# prototype2.net
KiCad netlist of a schematic drawn in EAGLE
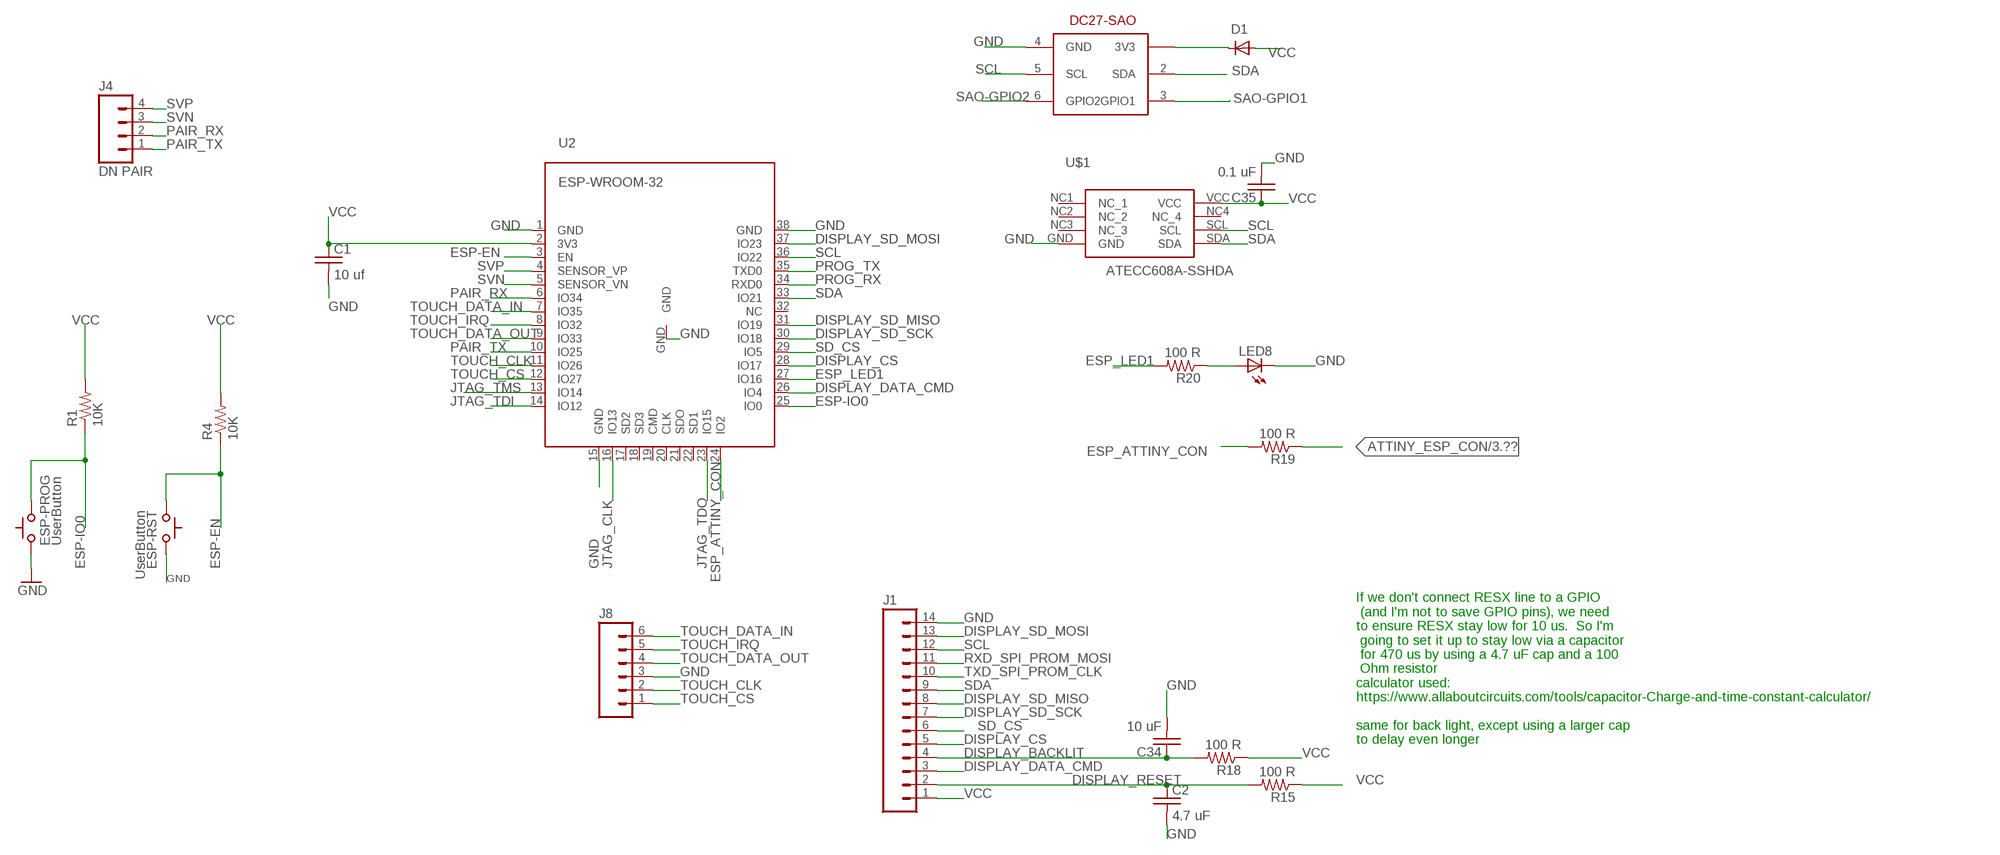
[diagram p0: schematic, sheet 1]
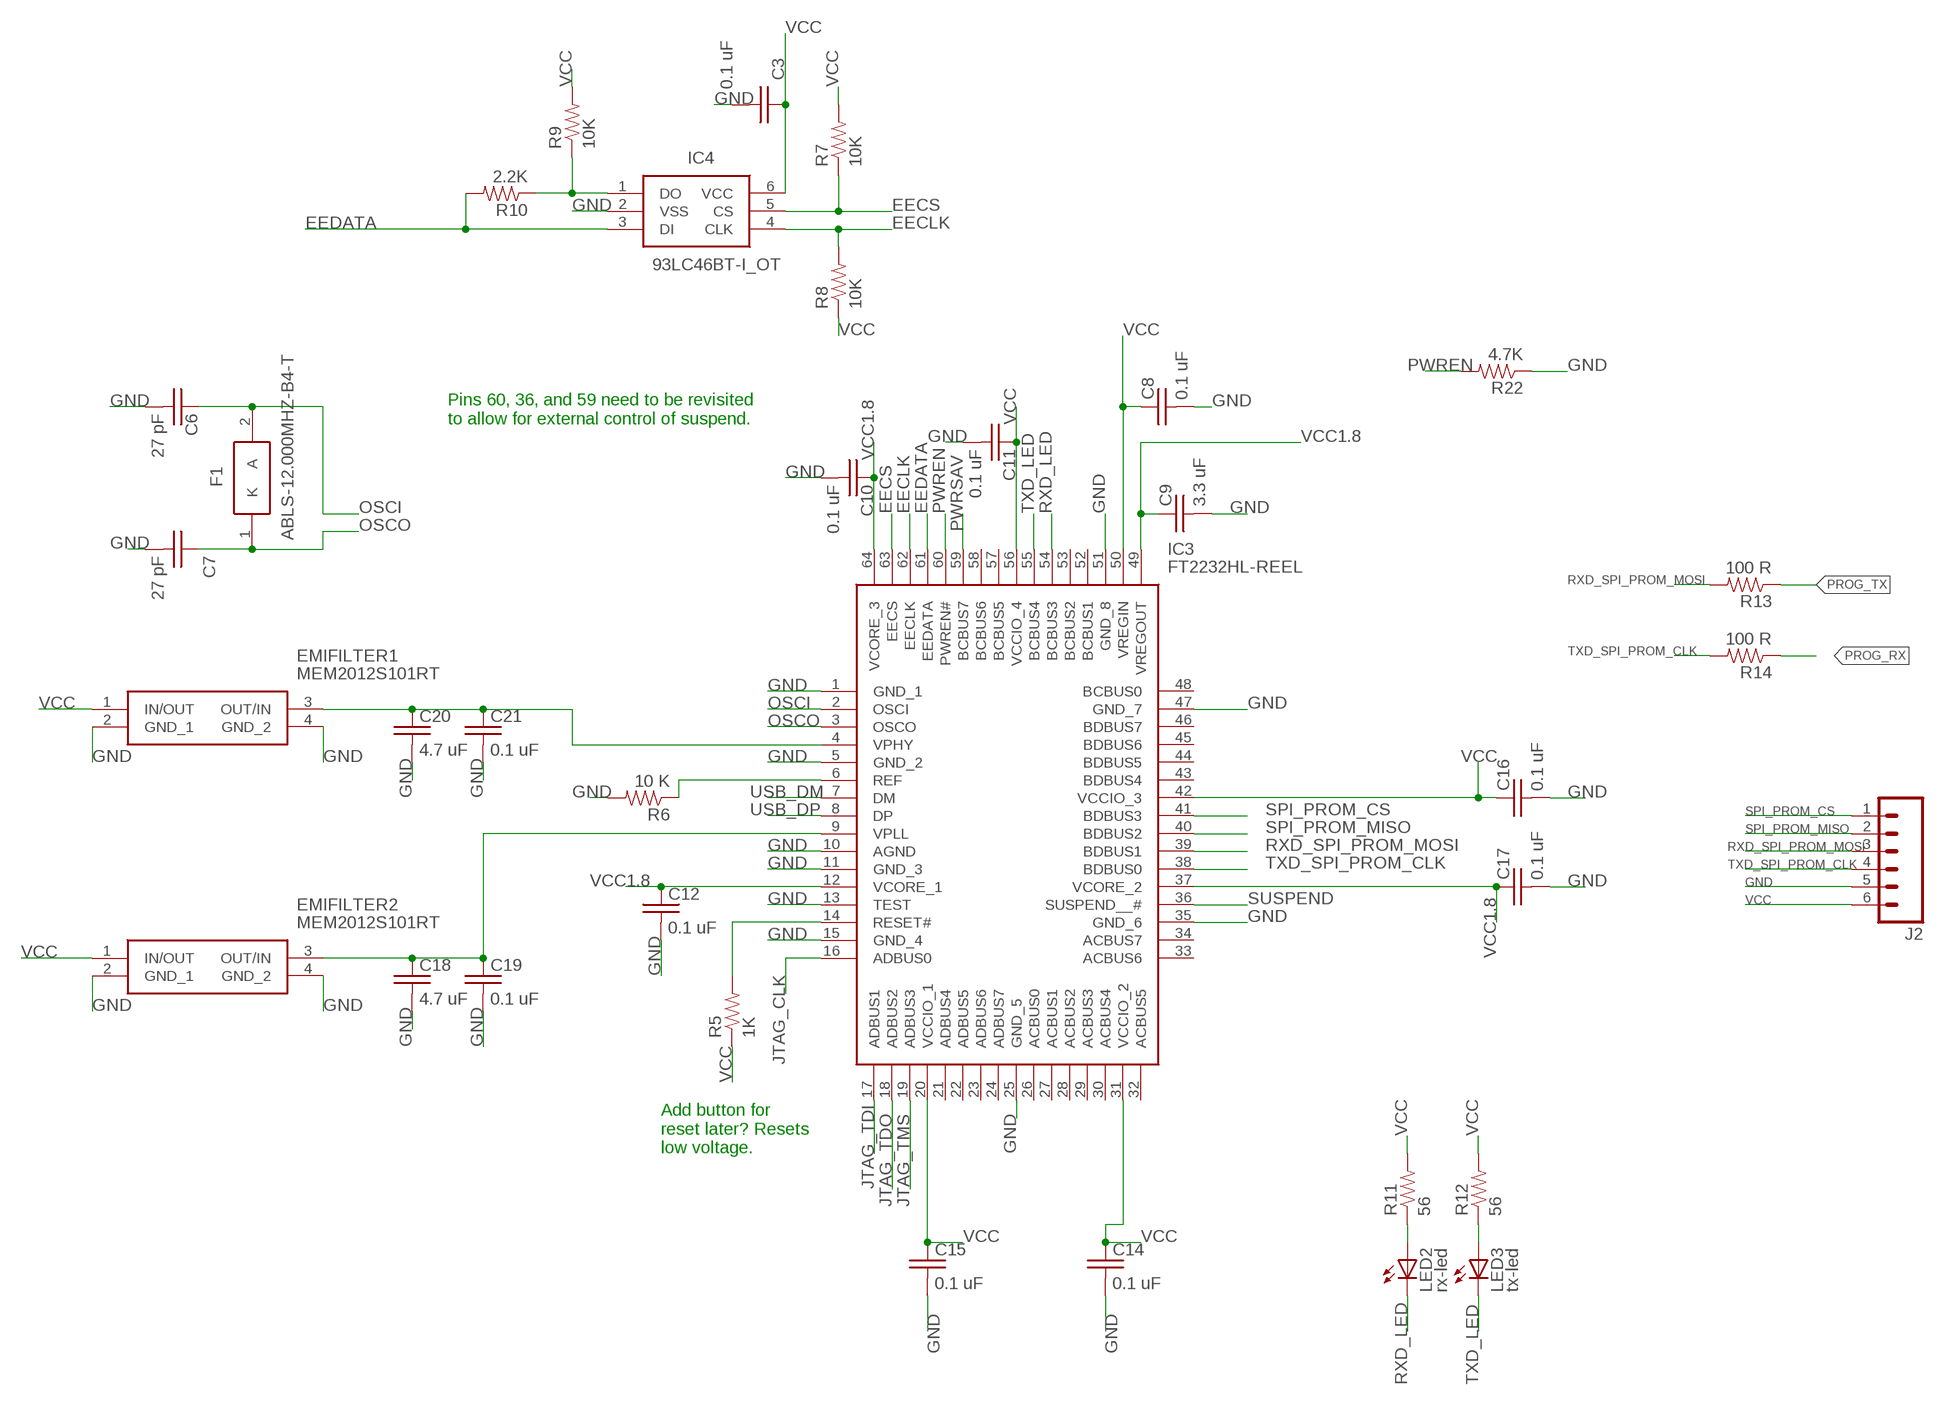
[diagram p1: schematic, sheet 2]
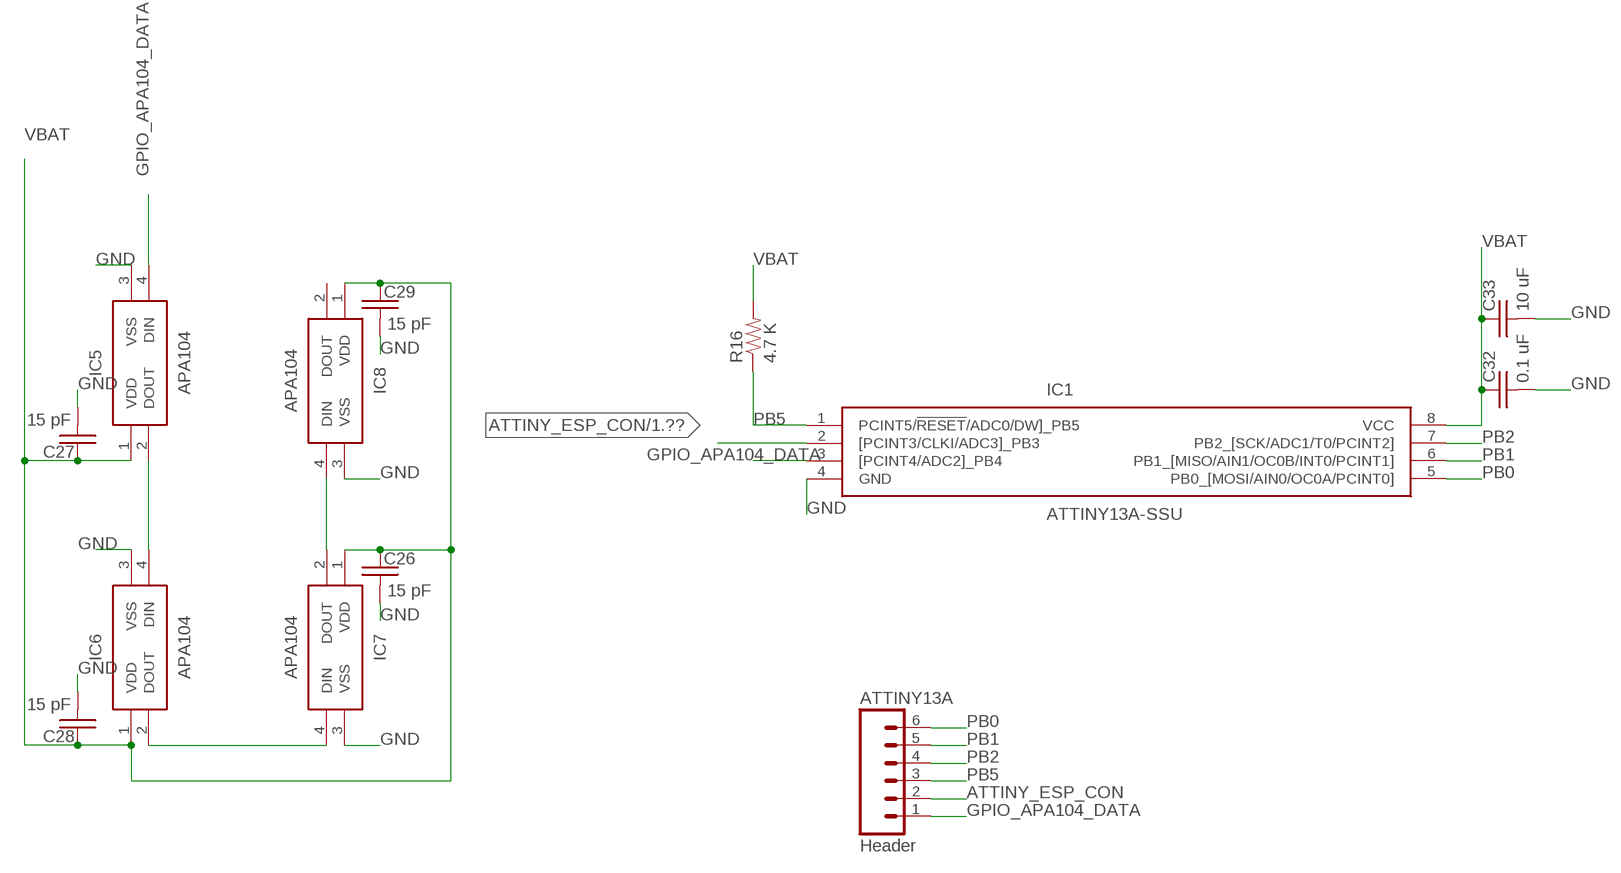
[diagram p2: schematic, sheet 3]
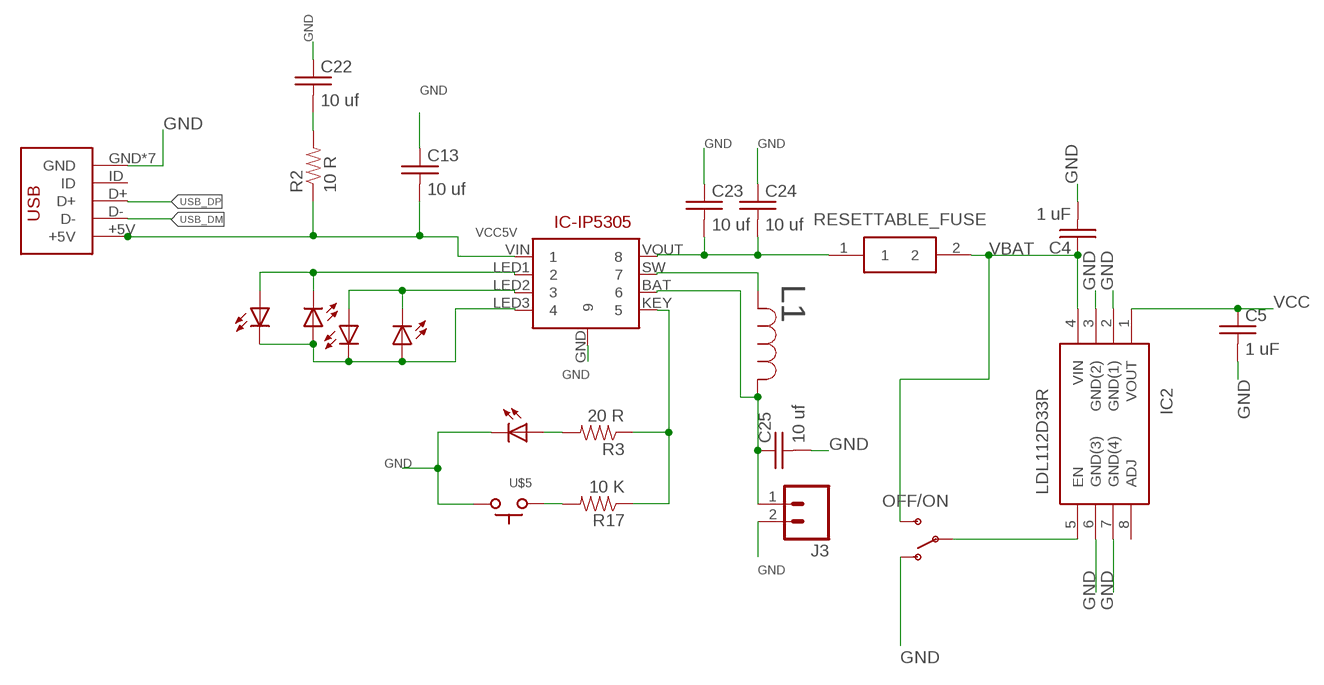
[diagram p3: schematic, sheet 4]
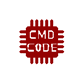
[diagram p4: schematic, sheet 5]

(export (version "E")
  (design (tool "Eeschema 10.0.6"))
  (components
    (comp (ref "ATTINY13A")
      (value "Header")
      (footprint "eagle-import:1X06")
      (libsource (lib "eagle-import") (part "M06SILK_FEMALE_PTH"))
    )
    (comp (ref "C26")
      (value "15 pF")
      (footprint "eagle-import:C0805")
      (libsource (lib "eagle-import") (part "C-USC0805"))
    )
    (comp (ref "C27")
      (value "15 pF")
      (footprint "eagle-import:C0805")
      (libsource (lib "eagle-import") (part "C-USC0805"))
    )
    (comp (ref "C28")
      (value "15 pF")
      (footprint "eagle-import:C0805")
      (libsource (lib "eagle-import") (part "C-USC0805"))
    )
    (comp (ref "C29")
      (value "15 pF")
      (footprint "eagle-import:C0805")
      (libsource (lib "eagle-import") (part "C-USC0805"))
    )
    (comp (ref "C32")
      (value "0.1 uF")
      (footprint "eagle-import:C0805")
      (libsource (lib "eagle-import") (part "C-USC0805"))
    )
    (comp (ref "C33")
      (value "10 uF")
      (footprint "eagle-import:C0805")
      (libsource (lib "eagle-import") (part "C-USC0805"))
    )
    (comp (ref "IC1")
      (value "ATTINY13A-SSU")
      (footprint "eagle-import:SOIC127P600X175-8N")
      (fields (field (name "MOUSER_PART_NUMBER") "556-ATTINY13A-SSU"))
      (libsource (lib "eagle-import") (part "ATTINY13A-SSU"))
    )
    (comp (ref "IC5")
      (value "APA104")
      (footprint "eagle-import:APA104")
      (libsource (lib "eagle-import") (part "APA104"))
    )
    (comp (ref "IC6")
      (value "APA104")
      (footprint "eagle-import:APA104")
      (libsource (lib "eagle-import") (part "APA104"))
    )
    (comp (ref "IC7")
      (value "APA104")
      (footprint "eagle-import:APA104")
      (libsource (lib "eagle-import") (part "APA104"))
    )
    (comp (ref "IC8")
      (value "APA104")
      (footprint "eagle-import:APA104")
      (libsource (lib "eagle-import") (part "APA104"))
    )
    (comp (ref "R16")
      (value "4.7 K")
      (footprint "eagle-import:0805")
      (libsource (lib "eagle-import") (part "passives_RESISTOR0805-RES"))
    )
    (comp (ref "U$3")
      (value "CMD_C0DE_LOGOCMD_CODE_LOGO_TOP_COPPER")
      (footprint "eagle-import:CMD_C0DE_LOGO_TOP_COPPER")
      (libsource (lib "eagle-import") (part "CMD_C0DE_LOGOCMD_CODE_LOGO_TOP_COPPER"))
    )
    (comp (ref "C1")
      (value "10 uf")
      (footprint "eagle-import:C0805")
      (libsource (lib "eagle-import") (part "C-USC0805"))
    )
    (comp (ref "C2")
      (value "4.7 uF")
      (footprint "eagle-import:C0805")
      (libsource (lib "eagle-import") (part "C-USC0805"))
    )
    (comp (ref "C34")
      (value "10 uF")
      (footprint "eagle-import:C0805")
      (libsource (lib "eagle-import") (part "C-USC0805"))
    )
    (comp (ref "C35")
      (value "0.1 uF")
      (footprint "eagle-import:C0805")
      (libsource (lib "eagle-import") (part "C-USC0805"))
    )
    (comp (ref "D1")
      (value "DIODESMA")
      (footprint "eagle-import:SMA-DIODE")
      (libsource (lib "eagle-import") (part "DIODESMA"))
    )
    (comp (ref "ESP-PROG")
      (value "UserButton")
      (footprint "eagle-import:TACTILE-2PIN-NARROW")
      (libsource (lib "eagle-import") (part "SWITCH_TACTILETACTILE-2PIN-NARROW"))
    )
    (comp (ref "ESP-RST")
      (value "UserButton")
      (footprint "eagle-import:TACTILE-2PIN-NARROW")
      (libsource (lib "eagle-import") (part "SWITCH_TACTILETACTILE-2PIN-NARROW"))
    )
    (comp (ref "J1")
      (value "M14")
      (footprint "eagle-import:1X14")
      (libsource (lib "eagle-import") (part "M14"))
    )
    (comp (ref "J4")
      (value "DN PAIR")
      (footprint "eagle-import:1X04")
      (libsource (lib "eagle-import") (part "M04PTH"))
    )
    (comp (ref "J8")
      (value "M06NO_SILK_YES_STOP")
      (footprint "eagle-import:1X06_NO_SILK_YES_STOP")
      (libsource (lib "eagle-import") (part "M06NO_SILK_YES_STOP"))
    )
    (comp (ref "LED8")
      (value "LED3MM")
      (footprint "eagle-import:LED3MM")
      (libsource (lib "eagle-import") (part "LED3MM"))
    )
    (comp (ref "R1")
      (value "10K")
      (footprint "eagle-import:0805")
      (libsource (lib "eagle-import") (part "RESISTOR0805-RES"))
    )
    (comp (ref "R4")
      (value "10K")
      (footprint "eagle-import:0805")
      (libsource (lib "eagle-import") (part "RESISTOR0805-RES"))
    )
    (comp (ref "R15")
      (value "100 R")
      (footprint "eagle-import:0805")
      (libsource (lib "eagle-import") (part "RESISTOR0805-RES"))
    )
    (comp (ref "R18")
      (value "100 R")
      (footprint "eagle-import:0805")
      (libsource (lib "eagle-import") (part "RESISTOR0805-RES"))
    )
    (comp (ref "R19")
      (value "100 R")
      (footprint "eagle-import:0805")
      (libsource (lib "eagle-import") (part "RESISTOR0805-RES"))
    )
    (comp (ref "R20")
      (value "100 R")
      (footprint "eagle-import:0805")
      (libsource (lib "eagle-import") (part "RESISTOR0805-RES"))
    )
    (comp (ref "U$1")
      (value "ATECC608A-SSHDA")
      (footprint "eagle-import:8-SOIC")
      (libsource (lib "eagle-import") (part "ATECC608A-SSHDA"))
    )
    (comp (ref "U$4")
      (value "DC-27-SAO")
      (footprint "eagle-import:3X2")
      (libsource (lib "eagle-import") (part "DC-27-SAO"))
    )
    (comp (ref "U2")
      (value "ESP-WROOM-32")
      (footprint "eagle-import:ESP-WROOM-32")
      (libsource (lib "eagle-import") (part "ESP-WROOM-32"))
    )
    (comp (ref "C3")
      (value "0.1 uF")
      (footprint "eagle-import:C0805")
      (libsource (lib "eagle-import") (part "C-USC0805"))
    )
    (comp (ref "C6")
      (value "27 pF")
      (footprint "eagle-import:C0805")
      (libsource (lib "eagle-import") (part "C-USC0805"))
    )
    (comp (ref "C7")
      (value "27 pF")
      (footprint "eagle-import:C0805")
      (libsource (lib "eagle-import") (part "C-USC0805"))
    )
    (comp (ref "C8")
      (value "0.1 uF")
      (footprint "eagle-import:C0805")
      (libsource (lib "eagle-import") (part "C-USC0805"))
    )
    (comp (ref "C9")
      (value "3.3 uF")
      (footprint "eagle-import:C0805")
      (libsource (lib "eagle-import") (part "C-USC0805"))
    )
    (comp (ref "C10")
      (value "0.1 uF")
      (footprint "eagle-import:C0805")
      (libsource (lib "eagle-import") (part "C-USC0805"))
    )
    (comp (ref "C11")
      (value "0.1 uF")
      (footprint "eagle-import:C0805")
      (libsource (lib "eagle-import") (part "C-USC0805"))
    )
    (comp (ref "C12")
      (value "0.1 uF")
      (footprint "eagle-import:C0805")
      (libsource (lib "eagle-import") (part "C-USC0805"))
    )
    (comp (ref "C14")
      (value "0.1 uF")
      (footprint "eagle-import:C0805")
      (libsource (lib "eagle-import") (part "C-USC0805"))
    )
    (comp (ref "C15")
      (value "0.1 uF")
      (footprint "eagle-import:C0805")
      (libsource (lib "eagle-import") (part "C-USC0805"))
    )
    (comp (ref "C16")
      (value "0.1 uF")
      (footprint "eagle-import:C0805")
      (libsource (lib "eagle-import") (part "C-USC0805"))
    )
    (comp (ref "C17")
      (value "0.1 uF")
      (footprint "eagle-import:C0805")
      (libsource (lib "eagle-import") (part "C-USC0805"))
    )
    (comp (ref "C18")
      (value "4.7 uF")
      (footprint "eagle-import:C0805")
      (libsource (lib "eagle-import") (part "C-USC0805"))
    )
    (comp (ref "C19")
      (value "0.1 uF")
      (footprint "eagle-import:C0805")
      (libsource (lib "eagle-import") (part "C-USC0805"))
    )
    (comp (ref "C20")
      (value "4.7 uF")
      (footprint "eagle-import:C0805")
      (libsource (lib "eagle-import") (part "C-USC0805"))
    )
    (comp (ref "C21")
      (value "0.1 uF")
      (footprint "eagle-import:C0805")
      (libsource (lib "eagle-import") (part "C-USC0805"))
    )
    (comp (ref "EMIFILTER1")
      (value "MEM2012S101RT")
      (footprint "eagle-import:MEM2012S101RT")
      (libsource (lib "eagle-import") (part "MEM2012S101RT"))
    )
    (comp (ref "EMIFILTER2")
      (value "MEM2012S101RT")
      (footprint "eagle-import:MEM2012S101RT")
      (libsource (lib "eagle-import") (part "MEM2012S101RT"))
    )
    (comp (ref "F1")
      (value "ABLS-12.000MHZ-B4-T")
      (footprint "eagle-import:HC_49US-(AT49)_1")
      (fields
        (field (name "MOUSER_PART_NUMBER") "815-ABLS-12.0M-T")
        (field (name "RS_PART_NUMBER") "1710207")
      )
      (libsource (lib "eagle-import") (part "ABLS-12.000MHZ-B4-T"))
    )
    (comp (ref "IC3")
      (value "FT2232HL-REEL")
      (footprint "eagle-import:QFP50P1200X1200X160-64N")
      (fields (field (name "MOUSER_PART_NUMBER") "895-FT2232HL"))
      (libsource (lib "eagle-import") (part "FT2232HL-REEL"))
    )
    (comp (ref "IC4")
      (value "93LC46BT-I_OT")
      (footprint "eagle-import:SOT95P270X145-6N")
      (fields
        (field (name "MANUFACTURER_PART_NUMBER") "93LC46BT-I/OT")
        (field (name "MOUSER_PART_NUMBER") "579-93LC46BT-I/OT")
      )
      (libsource (lib "eagle-import") (part "93LC46BT-I_OT"))
    )
    (comp (ref "J2")
      (value "M06SILK_FEMALE_PTH")
      (footprint "eagle-import:1X06")
      (libsource (lib "eagle-import") (part "M06SILK_FEMALE_PTH"))
    )
    (comp (ref "LED2")
      (value "rx-led")
      (footprint "eagle-import:LED3MM")
      (libsource (lib "eagle-import") (part "LED3MM"))
    )
    (comp (ref "LED3")
      (value "tx-led")
      (footprint "eagle-import:LED3MM")
      (libsource (lib "eagle-import") (part "LED3MM"))
    )
    (comp (ref "R5")
      (value "1K")
      (footprint "eagle-import:0805")
      (libsource (lib "eagle-import") (part "passives_RESISTOR0805-RES"))
    )
    (comp (ref "R6")
      (value "10 K")
      (footprint "eagle-import:0805")
      (libsource (lib "eagle-import") (part "passives_RESISTOR0805-RES"))
    )
    (comp (ref "R7")
      (value "10K")
      (footprint "eagle-import:0805")
      (libsource (lib "eagle-import") (part "passives_RESISTOR0805-RES"))
    )
    (comp (ref "R8")
      (value "10K")
      (footprint "eagle-import:0805")
      (libsource (lib "eagle-import") (part "passives_RESISTOR0805-RES"))
    )
    (comp (ref "R9")
      (value "10K")
      (footprint "eagle-import:0805")
      (libsource (lib "eagle-import") (part "passives_RESISTOR0805-RES"))
    )
    (comp (ref "R10")
      (value "2.2K")
      (footprint "eagle-import:0805")
      (libsource (lib "eagle-import") (part "passives_RESISTOR0805-RES"))
    )
    (comp (ref "R11")
      (value "56")
      (footprint "eagle-import:0805")
      (libsource (lib "eagle-import") (part "passives_RESISTOR0805-RES"))
    )
    (comp (ref "R12")
      (value "56")
      (footprint "eagle-import:0805")
      (libsource (lib "eagle-import") (part "passives_RESISTOR0805-RES"))
    )
    (comp (ref "R13")
      (value "100 R")
      (footprint "eagle-import:0805")
      (libsource (lib "eagle-import") (part "passives_RESISTOR0805-RES"))
    )
    (comp (ref "R14")
      (value "100 R")
      (footprint "eagle-import:0805")
      (libsource (lib "eagle-import") (part "passives_RESISTOR0805-RES"))
    )
    (comp (ref "R22")
      (value "4.7K")
      (footprint "eagle-import:0805")
      (libsource (lib "eagle-import") (part "passives_RESISTOR0805-RES"))
    )
    (comp (ref "C4")
      (value "1 uF")
      (footprint "eagle-import:C0805")
      (libsource (lib "eagle-import") (part "C-USC0805"))
    )
    (comp (ref "C5")
      (value "1 uF")
      (footprint "eagle-import:C0805")
      (libsource (lib "eagle-import") (part "C-USC0805"))
    )
    (comp (ref "C13")
      (value "10 uf")
      (footprint "eagle-import:C0805")
      (libsource (lib "eagle-import") (part "C-USC0805"))
    )
    (comp (ref "C22")
      (value "10 uf")
      (footprint "eagle-import:C0805")
      (libsource (lib "eagle-import") (part "C-USC0805"))
    )
    (comp (ref "C23")
      (value "10 uf")
      (footprint "eagle-import:C0805")
      (libsource (lib "eagle-import") (part "C-USC0805"))
    )
    (comp (ref "C24")
      (value "10 uf")
      (footprint "eagle-import:C0805")
      (libsource (lib "eagle-import") (part "C-USC0805"))
    )
    (comp (ref "C25")
      (value "10 uf")
      (footprint "eagle-import:C0805")
      (libsource (lib "eagle-import") (part "C-USC0805"))
    )
    (comp (ref "IC-IP5305")
      (value "IP5305ESOP8")
      (footprint "eagle-import:SOIC127P600X165-8")
      (libsource (lib "eagle-import") (part "IP5305ESOP8"))
    )
    (comp (ref "IC2")
      (value "LDL112D33R")
      (footprint "eagle-import:SOIC127P600X175-8N")
      (libsource (lib "eagle-import") (part "LDL112D33R"))
    )
    (comp (ref "J3")
      (value "M02PTH")
      (footprint "eagle-import:1X02")
      (libsource (lib "eagle-import") (part "M02PTH"))
    )
    (comp (ref "L1")
      (value "NRS4018T2R2MDGJ")
      (footprint "eagle-import:IND_TAIYO_NRS4018")
      (libsource (lib "eagle-import") (part "NRS4018T2R2MDGJ"))
    )
    (comp (ref "LED1")
      (value "LED3MM")
      (footprint "eagle-import:LED3MM")
      (libsource (lib "eagle-import") (part "LED3MM"))
    )
    (comp (ref "LED4")
      (value "LED3MM")
      (footprint "eagle-import:LED3MM")
      (libsource (lib "eagle-import") (part "LED3MM"))
    )
    (comp (ref "LED5")
      (value "LED3MM")
      (footprint "eagle-import:LED3MM")
      (libsource (lib "eagle-import") (part "LED3MM"))
    )
    (comp (ref "LED6")
      (value "LED3MM")
      (footprint "eagle-import:LED3MM")
      (libsource (lib "eagle-import") (part "LED3MM"))
    )
    (comp (ref "LED7")
      (value "LED3MM")
      (footprint "eagle-import:LED3MM")
      (libsource (lib "eagle-import") (part "LED3MM"))
    )
    (comp (ref "OFF/ON")
      (value "SWITCH-SPSTPTH")
      (footprint "eagle-import:SWITCH-SPDT")
      (libsource (lib "eagle-import") (part "SWITCH-SPSTPTH"))
    )
    (comp (ref "R2")
      (value "10 R")
      (footprint "eagle-import:0805")
      (libsource (lib "eagle-import") (part "passives_RESISTOR0805-RES"))
    )
    (comp (ref "R3")
      (value "20 R")
      (footprint "eagle-import:0805")
      (libsource (lib "eagle-import") (part "passives_RESISTOR0805-RES"))
    )
    (comp (ref "R17")
      (value "10 K")
      (footprint "eagle-import:0805")
      (libsource (lib "eagle-import") (part "passives_RESISTOR0805-RES"))
    )
    (comp (ref "RESETTABLE_FUSE")
      (value "0ZCJ0050FF2G")
      (footprint "eagle-import:FUSC3216X55N")
      (libsource (lib "eagle-import") (part "0ZCJ0050FF2G"))
    )
    (comp (ref "U$2")
      (value "DX4R005JJ2DX4R005JJ2")
      (footprint "eagle-import:DX4R005JJ2")
      (libsource (lib "eagle-import") (part "DX4R005JJ2DX4R005JJ2"))
    )
    (comp (ref "U$5")
      (value "SWITCH_TACTILETACTILE-2PIN-NARROW")
      (footprint "eagle-import:TACTILE-2PIN-NARROW")
      (libsource (lib "eagle-import") (part "switches_SWITCH_TACTILETACTILE-2PIN-NARROW"))
    )
  )
  (nets
    (net (code "1") (name "ATTINY_ESP_CON") (class "Default")
      (node (ref "ATTINY13A") (pin "2") (pinfunction "2_2") (pintype "passive"))
      (node (ref "IC1") (pin "2") (pinfunction "[PCINT3/CLKI/ADC3]_PB3_2") (pintype "input"))
      (node (ref "R19") (pin "1") (pinfunction "1_1") (pintype "passive"))
    )
    (net (code "2") (name "DISPLAY_BACKLIT") (class "Default")
      (node (ref "C34") (pin "1") (pinfunction "1_1") (pintype "passive"))
      (node (ref "J1") (pin "4") (pinfunction "4_4") (pintype "passive"))
      (node (ref "R18") (pin "2") (pinfunction "2_2") (pintype "passive"))
    )
    (net (code "3") (name "DISPLAY_CS") (class "Default")
      (node (ref "J1") (pin "5") (pinfunction "5_5") (pintype "passive"))
      (node (ref "U2") (pin "28") (pinfunction "IO17_28") (pintype "bidirectional"))
    )
    (net (code "4") (name "DISPLAY_DATA_CMD") (class "Default")
      (node (ref "J1") (pin "3") (pinfunction "3_3") (pintype "passive"))
      (node (ref "U2") (pin "26") (pinfunction "IO4_26") (pintype "bidirectional"))
    )
    (net (code "5") (name "DISPLAY_RESET") (class "Default")
      (node (ref "C2") (pin "1") (pinfunction "1_1") (pintype "passive"))
      (node (ref "J1") (pin "2") (pinfunction "2_2") (pintype "passive"))
      (node (ref "R15") (pin "2") (pinfunction "2_2") (pintype "passive"))
    )
    (net (code "6") (name "DISPLAY_SD_MISO") (class "Default")
      (node (ref "J1") (pin "8") (pinfunction "8_8") (pintype "passive"))
      (node (ref "U2") (pin "31") (pinfunction "IO19_31") (pintype "bidirectional"))
    )
    (net (code "7") (name "DISPLAY_SD_MOSI") (class "Default")
      (node (ref "J1") (pin "13") (pinfunction "13_13") (pintype "passive"))
      (node (ref "U2") (pin "37") (pinfunction "IO23_37") (pintype "bidirectional"))
    )
    (net (code "8") (name "DISPLAY_SD_SCK") (class "Default")
      (node (ref "J1") (pin "7") (pinfunction "7_7") (pintype "passive"))
      (node (ref "U2") (pin "30") (pinfunction "IO18_30") (pintype "bidirectional"))
    )
    (net (code "9") (name "EECLK") (class "Default")
      (node (ref "IC3") (pin "62") (pinfunction "EECLK_62") (pintype "bidirectional"))
      (node (ref "IC4") (pin "4") (pinfunction "CLK_4") (pintype "input"))
      (node (ref "R8") (pin "2") (pinfunction "2_2") (pintype "passive"))
    )
    (net (code "10") (name "EECS") (class "Default")
      (node (ref "IC3") (pin "63") (pinfunction "EECS_63") (pintype "bidirectional"))
      (node (ref "IC4") (pin "5") (pinfunction "CS_5") (pintype "input"))
      (node (ref "R7") (pin "1") (pinfunction "1_1") (pintype "passive"))
    )
    (net (code "11") (name "EEDATA") (class "Default")
      (node (ref "IC3") (pin "61") (pinfunction "EEDATA_61") (pintype "bidirectional"))
      (node (ref "IC4") (pin "3") (pinfunction "DI_3") (pintype "bidirectional"))
      (node (ref "R10") (pin "2") (pinfunction "2_2") (pintype "passive"))
    )
    (net (code "12") (name "ESP-EN") (class "Default")
      (node (ref "ESP-RST") (pin "P$2") (pinfunction "C_P$2") (pintype "passive"))
      (node (ref "R4") (pin "1") (pinfunction "1_1") (pintype "passive"))
      (node (ref "U2") (pin "3") (pinfunction "EN_3") (pintype "bidirectional"))
    )
    (net (code "13") (name "ESP-IO0") (class "Default")
      (node (ref "ESP-PROG") (pin "P$1") (pinfunction "A_P$1") (pintype "passive"))
      (node (ref "R1") (pin "1") (pinfunction "1_1") (pintype "passive"))
      (node (ref "U2") (pin "25") (pinfunction "IO0_25") (pintype "bidirectional"))
    )
    (net (code "14") (name "ESP_ATTINY_CON") (class "Default")
      (node (ref "R19") (pin "2") (pinfunction "2_2") (pintype "passive"))
      (node (ref "U2") (pin "24") (pinfunction "IO2_24") (pintype "bidirectional"))
    )
    (net (code "15") (name "ESP_LED1") (class "Default")
      (node (ref "R20") (pin "2") (pinfunction "2_2") (pintype "passive"))
      (node (ref "U2") (pin "27") (pinfunction "IO16_27") (pintype "bidirectional"))
    )
    (net (code "16") (name "GND") (class "Default")
      (node (ref "C1") (pin "2") (pinfunction "2_2") (pintype "passive"))
      (node (ref "C10") (pin "2") (pinfunction "2_2") (pintype "passive"))
      (node (ref "C11") (pin "2") (pinfunction "2_2") (pintype "passive"))
      (node (ref "C12") (pin "2") (pinfunction "2_2") (pintype "passive"))
      (node (ref "C13") (pin "1") (pinfunction "1_1") (pintype "passive"))
      (node (ref "C14") (pin "2") (pinfunction "2_2") (pintype "passive"))
      (node (ref "C15") (pin "2") (pinfunction "2_2") (pintype "passive"))
      (node (ref "C16") (pin "2") (pinfunction "2_2") (pintype "passive"))
      (node (ref "C17") (pin "2") (pinfunction "2_2") (pintype "passive"))
      (node (ref "C18") (pin "2") (pinfunction "2_2") (pintype "passive"))
      (node (ref "C19") (pin "2") (pinfunction "2_2") (pintype "passive"))
      (node (ref "C2") (pin "2") (pinfunction "2_2") (pintype "passive"))
      (node (ref "C20") (pin "2") (pinfunction "2_2") (pintype "passive"))
      (node (ref "C21") (pin "2") (pinfunction "2_2") (pintype "passive"))
      (node (ref "C22") (pin "1") (pinfunction "1_1") (pintype "passive"))
      (node (ref "C23") (pin "1") (pinfunction "1_1") (pintype "passive"))
      (node (ref "C24") (pin "1") (pinfunction "1_1") (pintype "passive"))
      (node (ref "C25") (pin "2") (pinfunction "2_2") (pintype "passive"))
      (node (ref "C26") (pin "2") (pinfunction "2_2") (pintype "passive"))
      (node (ref "C27") (pin "2") (pinfunction "2_2") (pintype "passive"))
      (node (ref "C28") (pin "2") (pinfunction "2_2") (pintype "passive"))
      (node (ref "C29") (pin "2") (pinfunction "2_2") (pintype "passive"))
      (node (ref "C3") (pin "2") (pinfunction "2_2") (pintype "passive"))
      (node (ref "C32") (pin "2") (pinfunction "2_2") (pintype "passive"))
      (node (ref "C33") (pin "2") (pinfunction "2_2") (pintype "passive"))
      (node (ref "C34") (pin "2") (pinfunction "2_2") (pintype "passive"))
      (node (ref "C35") (pin "2") (pinfunction "2_2") (pintype "passive"))
      (node (ref "C4") (pin "2") (pinfunction "2_2") (pintype "passive"))
      (node (ref "C5") (pin "2") (pinfunction "2_2") (pintype "passive"))
      (node (ref "C6") (pin "2") (pinfunction "2_2") (pintype "passive"))
      (node (ref "C7") (pin "2") (pinfunction "2_2") (pintype "passive"))
      (node (ref "C8") (pin "2") (pinfunction "2_2") (pintype "passive"))
      (node (ref "C9") (pin "2") (pinfunction "2_2") (pintype "passive"))
      (node (ref "EMIFILTER1") (pin "2") (pinfunction "GND_1_2") (pintype "bidirectional"))
      (node (ref "EMIFILTER1") (pin "4") (pinfunction "GND_2_4") (pintype "bidirectional"))
      (node (ref "EMIFILTER2") (pin "2") (pinfunction "GND_1_2") (pintype "bidirectional"))
      (node (ref "EMIFILTER2") (pin "4") (pinfunction "GND_2_4") (pintype "bidirectional"))
      (node (ref "ESP-PROG") (pin "P$2") (pinfunction "C_P$2") (pintype "passive"))
      (node (ref "ESP-RST") (pin "P$1") (pinfunction "A_P$1") (pintype "passive"))
      (node (ref "IC-IP5305") (pin "GND") (pinfunction "9_GND") (pintype "power_in"))
      (node (ref "IC1") (pin "4") (pinfunction "GND_4") (pintype "power_in"))
      (node (ref "IC2") (pin "2") (pinfunction "GND(1)_2") (pintype "bidirectional"))
      (node (ref "IC2") (pin "3") (pinfunction "GND(2)_3") (pintype "bidirectional"))
      (node (ref "IC2") (pin "6") (pinfunction "GND(3)_6") (pintype "bidirectional"))
      (node (ref "IC2") (pin "7") (pinfunction "GND(4)_7") (pintype "bidirectional"))
      (node (ref "IC3") (pin "1") (pinfunction "GND_1_1") (pintype "bidirectional"))
      (node (ref "IC3") (pin "10") (pinfunction "AGND_10") (pintype "bidirectional"))
      (node (ref "IC3") (pin "11") (pinfunction "GND_3_11") (pintype "bidirectional"))
      (node (ref "IC3") (pin "13") (pinfunction "TEST_13") (pintype "bidirectional"))
      (node (ref "IC3") (pin "15") (pinfunction "GND_4_15") (pintype "bidirectional"))
      (node (ref "IC3") (pin "25") (pinfunction "GND_5_25") (pintype "bidirectional"))
      (node (ref "IC3") (pin "35") (pinfunction "GND_6_35") (pintype "bidirectional"))
      (node (ref "IC3") (pin "47") (pinfunction "GND_7_47") (pintype "bidirectional"))
      (node (ref "IC3") (pin "5") (pinfunction "GND_2_5") (pintype "bidirectional"))
      (node (ref "IC3") (pin "51") (pinfunction "GND_8_51") (pintype "bidirectional"))
      (node (ref "IC4") (pin "2") (pinfunction "VSS_2") (pintype "power_in"))
      (node (ref "IC5") (pin "3") (pinfunction "VSS_3") (pintype "power_in"))
      (node (ref "IC6") (pin "3") (pinfunction "VSS_3") (pintype "power_in"))
      (node (ref "IC7") (pin "3") (pinfunction "VSS_3") (pintype "power_in"))
      (node (ref "IC8") (pin "3") (pinfunction "VSS_3") (pintype "power_in"))
      (node (ref "J1") (pin "14") (pinfunction "14_14") (pintype "passive"))
      (node (ref "J2") (pin "5") (pinfunction "5_5") (pintype "passive"))
      (node (ref "J3") (pin "2") (pinfunction "2_2") (pintype "passive"))
      (node (ref "J8") (pin "3") (pinfunction "3_3") (pintype "passive"))
      (node (ref "LED7") (pin "K") (pinfunction "C_K") (pintype "output"))
      (node (ref "LED8") (pin "K") (pinfunction "C_K") (pintype "output"))
      (node (ref "OFF/ON") (pin "1") (pinfunction "O_1") (pintype "passive"))
      (node (ref "R22") (pin "1") (pinfunction "1_1") (pintype "passive"))
      (node (ref "R6") (pin "2") (pinfunction "2_2") (pintype "passive"))
      (node (ref "U$1") (pin "GND") (pinfunction "GND_GND") (pintype "power_in"))
      (node (ref "U$2") (pin "GND") (pinfunction "GND_GND") (pintype "bidirectional"))
      (node (ref "U$2") (pin "P$10") (pinfunction "GND_P$10") (pintype "bidirectional"))
      (node (ref "U$2") (pin "P$11") (pinfunction "GND_P$11") (pintype "bidirectional"))
      (node (ref "U$2") (pin "P$6") (pinfunction "GND_P$6") (pintype "bidirectional"))
      (node (ref "U$2") (pin "P$7") (pinfunction "GND_P$7") (pintype "bidirectional"))
      (node (ref "U$2") (pin "P$8") (pinfunction "GND_P$8") (pintype "bidirectional"))
      (node (ref "U$2") (pin "P$9") (pinfunction "GND_P$9") (pintype "bidirectional"))
      (node (ref "U$4") (pin "4") (pinfunction "GND_4") (pintype "power_in"))
      (node (ref "U$5") (pin "P$1") (pinfunction "A_P$1") (pintype "passive"))
      (node (ref "U2") (pin "1") (pinfunction "GND_1") (pintype "bidirectional"))
      (node (ref "U2") (pin "15") (pinfunction "GND_15") (pintype "bidirectional"))
      (node (ref "U2") (pin "38") (pinfunction "GND_38") (pintype "bidirectional"))
      (node (ref "U2") (pin "GND") (pinfunction "GND_GND") (pintype "bidirectional"))
    )
    (net (code "17") (name "GPIO_APA104_DATA") (class "Default")
      (node (ref "ATTINY13A") (pin "1") (pinfunction "1_1") (pintype "passive"))
      (node (ref "IC1") (pin "3") (pinfunction "[PCINT4/ADC2]_PB4_3") (pintype "input"))
      (node (ref "IC5") (pin "4") (pinfunction "DIN_4") (pintype "input"))
    )
    (net (code "18") (name "JTAG_CLK") (class "Default")
      (node (ref "IC3") (pin "16") (pinfunction "ADBUS0_16") (pintype "bidirectional"))
      (node (ref "U2") (pin "16") (pinfunction "IO13_16") (pintype "bidirectional"))
    )
    (net (code "19") (name "JTAG_TDI") (class "Default")
      (node (ref "IC3") (pin "17") (pinfunction "ADBUS1_17") (pintype "bidirectional"))
      (node (ref "U2") (pin "14") (pinfunction "IO12_14") (pintype "bidirectional"))
    )
    (net (code "20") (name "JTAG_TDO") (class "Default")
      (node (ref "IC3") (pin "18") (pinfunction "ADBUS2_18") (pintype "bidirectional"))
      (node (ref "U2") (pin "23") (pinfunction "IO15_23") (pintype "bidirectional"))
    )
    (net (code "21") (name "JTAG_TMS") (class "Default")
      (node (ref "IC3") (pin "19") (pinfunction "ADBUS3_19") (pintype "bidirectional"))
      (node (ref "U2") (pin "13") (pinfunction "IO14_13") (pintype "bidirectional"))
    )
    (net (code "22") (name "Net-(C22-Pad2)") (class "Default")
      (node (ref "C22") (pin "2") (pinfunction "2_2") (pintype "passive"))
      (node (ref "R2") (pin "2") (pinfunction "2_2") (pintype "passive"))
    )
    (net (code "23") (name "Net-(EMIFILTER1-OUT{slash}IN)") (class "Default")
      (node (ref "C20") (pin "1") (pinfunction "1_1") (pintype "passive"))
      (node (ref "C21") (pin "1") (pinfunction "1_1") (pintype "passive"))
      (node (ref "EMIFILTER1") (pin "3") (pinfunction "OUT/IN_3") (pintype "bidirectional"))
      (node (ref "IC3") (pin "4") (pinfunction "VPHY_4") (pintype "bidirectional"))
    )
    (net (code "24") (name "Net-(EMIFILTER2-OUT{slash}IN)") (class "Default")
      (node (ref "C18") (pin "1") (pinfunction "1_1") (pintype "passive"))
      (node (ref "C19") (pin "1") (pinfunction "1_1") (pintype "passive"))
      (node (ref "EMIFILTER2") (pin "3") (pinfunction "OUT/IN_3") (pintype "bidirectional"))
      (node (ref "IC3") (pin "9") (pinfunction "VPLL_9") (pintype "bidirectional"))
    )
    (net (code "25") (name "Net-(IC-IP5305-2)") (class "Default")
      (node (ref "IC-IP5305") (pin "LED1") (pinfunction "2_LED1") (pintype "output"))
      (node (ref "LED1") (pin "A") (pinfunction "A_A") (pintype "input"))
      (node (ref "LED4") (pin "K") (pinfunction "C_K") (pintype "output"))
    )
    (net (code "26") (name "Net-(IC-IP5305-3)") (class "Default")
      (node (ref "IC-IP5305") (pin "LED2") (pinfunction "3_LED2") (pintype "output"))
      (node (ref "LED5") (pin "A") (pinfunction "A_A") (pintype "input"))
      (node (ref "LED6") (pin "K") (pinfunction "C_K") (pintype "output"))
    )
    (net (code "27") (name "Net-(IC-IP5305-4)") (class "Default")
      (node (ref "IC-IP5305") (pin "LED3") (pinfunction "4_LED3") (pintype "output"))
      (node (ref "LED1") (pin "K") (pinfunction "C_K") (pintype "output"))
      (node (ref "LED4") (pin "A") (pinfunction "A_A") (pintype "input"))
      (node (ref "LED5") (pin "K") (pinfunction "C_K") (pintype "output"))
      (node (ref "LED6") (pin "A") (pinfunction "A_A") (pintype "input"))
    )
    (net (code "28") (name "Net-(IC-IP5305-5)") (class "Default")
      (node (ref "IC-IP5305") (pin "KEY") (pinfunction "5_KEY") (pintype "bidirectional"))
      (node (ref "R17") (pin "1") (pinfunction "1_1") (pintype "passive"))
      (node (ref "R3") (pin "1") (pinfunction "1_1") (pintype "passive"))
    )
    (net (code "29") (name "Net-(IC-IP5305-6)") (class "Default")
      (node (ref "C25") (pin "1") (pinfunction "1_1") (pintype "passive"))
      (node (ref "IC-IP5305") (pin "BAT") (pinfunction "6_BAT") (pintype "bidirectional"))
      (node (ref "J3") (pin "1") (pinfunction "1_1") (pintype "passive"))
      (node (ref "L1") (pin "1") (pinfunction "1_1") (pintype "passive"))
    )
    (net (code "30") (name "Net-(IC-IP5305-7)") (class "Default")
      (node (ref "IC-IP5305") (pin "SW") (pinfunction "7_SW") (pintype "bidirectional"))
      (node (ref "L1") (pin "2") (pinfunction "2_2") (pintype "passive"))
    )
    (net (code "31") (name "Net-(IC-IP5305-8)") (class "Default")
      (node (ref "C23") (pin "2") (pinfunction "2_2") (pintype "passive"))
      (node (ref "C24") (pin "2") (pinfunction "2_2") (pintype "passive"))
      (node (ref "IC-IP5305") (pin "VOUT") (pinfunction "8_VOUT") (pintype "bidirectional"))
      (node (ref "RESETTABLE_FUSE") (pin "1") (pinfunction "1_1") (pintype "passive"))
    )
    (net (code "32") (name "Net-(IC2-EN)") (class "Default")
      (node (ref "IC2") (pin "5") (pinfunction "EN_5") (pintype "bidirectional"))
      (node (ref "OFF/ON") (pin "2") (pinfunction "P_2") (pintype "passive"))
    )
    (net (code "33") (name "Net-(IC3-REF)") (class "Default")
      (node (ref "IC3") (pin "6") (pinfunction "REF_6") (pintype "bidirectional"))
      (node (ref "R6") (pin "1") (pinfunction "1_1") (pintype "passive"))
    )
    (net (code "34") (name "Net-(IC3-RESET#)") (class "Default")
      (node (ref "IC3") (pin "14") (pinfunction "RESET#_14") (pintype "bidirectional"))
      (node (ref "R5") (pin "2") (pinfunction "2_2") (pintype "passive"))
    )
    (net (code "35") (name "Net-(IC4-DO)") (class "Default")
      (node (ref "IC4") (pin "1") (pinfunction "DO_1") (pintype "bidirectional"))
      (node (ref "R10") (pin "1") (pinfunction "1_1") (pintype "passive"))
      (node (ref "R9") (pin "1") (pinfunction "1_1") (pintype "passive"))
    )
    (net (code "36") (name "Net-(IC5-DOUT)") (class "Default")
      (node (ref "IC5") (pin "2") (pinfunction "DOUT_2") (pintype "output"))
      (node (ref "IC6") (pin "4") (pinfunction "DIN_4") (pintype "input"))
    )
    (net (code "37") (name "Net-(IC6-DOUT)") (class "Default")
      (node (ref "IC6") (pin "2") (pinfunction "DOUT_2") (pintype "output"))
      (node (ref "IC7") (pin "4") (pinfunction "DIN_4") (pintype "input"))
    )
    (net (code "38") (name "Net-(IC7-DOUT)") (class "Default")
      (node (ref "IC7") (pin "2") (pinfunction "DOUT_2") (pintype "output"))
      (node (ref "IC8") (pin "4") (pinfunction "DIN_4") (pintype "input"))
    )
    (net (code "39") (name "Net-(LED2-PadA)") (class "Default")
      (node (ref "LED2") (pin "A") (pinfunction "A_A") (pintype "input"))
      (node (ref "R11") (pin "1") (pinfunction "1_1") (pintype "passive"))
    )
    (net (code "40") (name "Net-(LED3-PadA)") (class "Default")
      (node (ref "LED3") (pin "A") (pinfunction "A_A") (pintype "input"))
      (node (ref "R12") (pin "1") (pinfunction "1_1") (pintype "passive"))
    )
    (net (code "41") (name "Net-(LED7-PadA)") (class "Default")
      (node (ref "LED7") (pin "A") (pinfunction "A_A") (pintype "input"))
      (node (ref "R3") (pin "2") (pinfunction "2_2") (pintype "passive"))
    )
    (net (code "42") (name "Net-(LED8-PadA)") (class "Default")
      (node (ref "LED8") (pin "A") (pinfunction "A_A") (pintype "input"))
      (node (ref "R20") (pin "1") (pinfunction "1_1") (pintype "passive"))
    )
    (net (code "43") (name "Net-(U$4-3V3)") (class "Default")
      (node (ref "D1") (pin "C") (pinfunction "C_C") (pintype "passive"))
      (node (ref "U$4") (pin "1") (pinfunction "3V3_1") (pintype "power_in"))
    )
    (net (code "44") (name "Net-(U$5-C)") (class "Default")
      (node (ref "R17") (pin "2") (pinfunction "2_2") (pintype "passive"))
      (node (ref "U$5") (pin "P$2") (pinfunction "C_P$2") (pintype "passive"))
    )
    (net (code "45") (name "OSCI") (class "Default")
      (node (ref "C6") (pin "1") (pinfunction "1_1") (pintype "passive"))
      (node (ref "F1") (pin "2") (pinfunction "A_2") (pintype "bidirectional"))
      (node (ref "IC3") (pin "2") (pinfunction "OSCI_2") (pintype "bidirectional"))
    )
    (net (code "46") (name "OSCO") (class "Default")
      (node (ref "C7") (pin "1") (pinfunction "1_1") (pintype "passive"))
      (node (ref "F1") (pin "1") (pinfunction "K_1") (pintype "bidirectional"))
      (node (ref "IC3") (pin "3") (pinfunction "OSCO_3") (pintype "bidirectional"))
    )
    (net (code "47") (name "PAIR_RX") (class "Default")
      (node (ref "J4") (pin "2") (pinfunction "2_2") (pintype "passive"))
      (node (ref "U2") (pin "6") (pinfunction "IO34_6") (pintype "bidirectional"))
    )
    (net (code "48") (name "PAIR_TX") (class "Default")
      (node (ref "J4") (pin "1") (pinfunction "1_1") (pintype "passive"))
      (node (ref "U2") (pin "10") (pinfunction "IO25_10") (pintype "bidirectional"))
    )
    (net (code "49") (name "PB0") (class "Default")
      (node (ref "ATTINY13A") (pin "6") (pinfunction "6_6") (pintype "passive"))
      (node (ref "IC1") (pin "5") (pinfunction "PB0_[MOSI/AIN0/OC0A/PCINT0]_5") (pintype "input"))
    )
    (net (code "50") (name "PB1") (class "Default")
      (node (ref "ATTINY13A") (pin "5") (pinfunction "5_5") (pintype "passive"))
      (node (ref "IC1") (pin "6") (pinfunction "PB1_[MISO/AIN1/OC0B/INT0/PCINT1]_6") (pintype "input"))
    )
    (net (code "51") (name "PB2") (class "Default")
      (node (ref "ATTINY13A") (pin "4") (pinfunction "4_4") (pintype "passive"))
      (node (ref "IC1") (pin "7") (pinfunction "PB2_[SCK/ADC1/T0/PCINT2]_7") (pintype "input"))
    )
    (net (code "52") (name "PB5") (class "Default")
      (node (ref "ATTINY13A") (pin "3") (pinfunction "3_3") (pintype "passive"))
      (node (ref "IC1") (pin "1") (pinfunction "PCINT5/~{RESET}/ADC0/DW]_PB5_1") (pintype "input"))
      (node (ref "R16") (pin "1") (pinfunction "1_1") (pintype "passive"))
    )
    (net (code "53") (name "PROG_RX") (class "Default")
      (node (ref "R14") (pin "1") (pinfunction "1_1") (pintype "passive"))
      (node (ref "U2") (pin "34") (pinfunction "RXD0_34") (pintype "bidirectional"))
    )
    (net (code "54") (name "PROG_TX") (class "Default")
      (node (ref "R13") (pin "1") (pinfunction "1_1") (pintype "passive"))
      (node (ref "U2") (pin "35") (pinfunction "TXD0_35") (pintype "bidirectional"))
    )
    (net (code "55") (name "PWREN") (class "Default")
      (node (ref "IC3") (pin "60") (pinfunction "PWREN#_60") (pintype "bidirectional"))
      (node (ref "R22") (pin "2") (pinfunction "2_2") (pintype "passive"))
    )
    (net (code "56") (name "PWRSAV") (class "Default")
      (node (ref "IC3") (pin "59") (pinfunction "BCBUS7_59") (pintype "bidirectional"))
    )
    (net (code "57") (name "RXD_LED") (class "Default")
      (node (ref "IC3") (pin "54") (pinfunction "BCBUS3_54") (pintype "bidirectional"))
      (node (ref "LED2") (pin "K") (pinfunction "C_K") (pintype "output"))
    )
    (net (code "58") (name "RXD_SPI_PROM_MOSI") (class "Default")
      (node (ref "IC3") (pin "39") (pinfunction "BDBUS1_39") (pintype "bidirectional"))
      (node (ref "J1") (pin "11") (pinfunction "11_11") (pintype "passive"))
      (node (ref "J2") (pin "3") (pinfunction "3_3") (pintype "passive"))
      (node (ref "R13") (pin "2") (pinfunction "2_2") (pintype "passive"))
    )
    (net (code "59") (name "SAO-GPIO1") (class "Default")
      (node (ref "U$4") (pin "3") (pinfunction "GPIO1_3") (pintype "bidirectional"))
    )
    (net (code "60") (name "SAO-GPIO2") (class "Default")
      (node (ref "U$4") (pin "6") (pinfunction "GPIO2_6") (pintype "bidirectional"))
    )
    (net (code "61") (name "SCL") (class "Default")
      (node (ref "J1") (pin "12") (pinfunction "12_12") (pintype "passive"))
      (node (ref "U$1") (pin "SCL") (pinfunction "SCL_SCL") (pintype "bidirectional"))
      (node (ref "U$4") (pin "5") (pinfunction "SCL_5") (pintype "bidirectional"))
      (node (ref "U2") (pin "36") (pinfunction "IO22_36") (pintype "bidirectional"))
    )
    (net (code "62") (name "SDA") (class "Default")
      (node (ref "J1") (pin "9") (pinfunction "9_9") (pintype "passive"))
      (node (ref "U$1") (pin "SDA") (pinfunction "SDA_SDA") (pintype "bidirectional"))
      (node (ref "U$4") (pin "2") (pinfunction "SDA_2") (pintype "bidirectional"))
      (node (ref "U2") (pin "33") (pinfunction "IO21_33") (pintype "bidirectional"))
    )
    (net (code "63") (name "SD_CS") (class "Default")
      (node (ref "J1") (pin "6") (pinfunction "6_6") (pintype "passive"))
      (node (ref "U2") (pin "29") (pinfunction "IO5_29") (pintype "bidirectional"))
    )
    (net (code "64") (name "SPI_PROM_CS") (class "Default")
      (node (ref "IC3") (pin "41") (pinfunction "BDBUS3_41") (pintype "bidirectional"))
      (node (ref "J2") (pin "1") (pinfunction "1_1") (pintype "passive"))
    )
    (net (code "65") (name "SPI_PROM_MISO") (class "Default")
      (node (ref "IC3") (pin "40") (pinfunction "BDBUS2_40") (pintype "bidirectional"))
      (node (ref "J2") (pin "2") (pinfunction "2_2") (pintype "passive"))
    )
    (net (code "66") (name "SUSPEND") (class "Default")
      (node (ref "IC3") (pin "36") (pinfunction "SUSPEND__#_36") (pintype "bidirectional"))
    )
    (net (code "67") (name "SVN") (class "Default")
      (node (ref "J4") (pin "3") (pinfunction "3_3") (pintype "passive"))
      (node (ref "U2") (pin "5") (pinfunction "SENSOR_VN_5") (pintype "bidirectional"))
    )
    (net (code "68") (name "SVP") (class "Default")
      (node (ref "J4") (pin "4") (pinfunction "4_4") (pintype "passive"))
      (node (ref "U2") (pin "4") (pinfunction "SENSOR_VP_4") (pintype "bidirectional"))
    )
    (net (code "69") (name "TOUCH_CLK") (class "Default")
      (node (ref "J8") (pin "2") (pinfunction "2_2") (pintype "passive"))
      (node (ref "U2") (pin "11") (pinfunction "IO26_11") (pintype "bidirectional"))
    )
    (net (code "70") (name "TOUCH_CS") (class "Default")
      (node (ref "J8") (pin "1") (pinfunction "1_1") (pintype "passive"))
      (node (ref "U2") (pin "12") (pinfunction "IO27_12") (pintype "bidirectional"))
    )
    (net (code "71") (name "TOUCH_DATA_IN") (class "Default")
      (node (ref "J8") (pin "6") (pinfunction "6_6") (pintype "passive"))
      (node (ref "U2") (pin "7") (pinfunction "IO35_7") (pintype "bidirectional"))
    )
    (net (code "72") (name "TOUCH_DATA_OUT") (class "Default")
      (node (ref "J8") (pin "4") (pinfunction "4_4") (pintype "passive"))
      (node (ref "U2") (pin "9") (pinfunction "IO33_9") (pintype "bidirectional"))
    )
    (net (code "73") (name "TOUCH_IRQ") (class "Default")
      (node (ref "J8") (pin "5") (pinfunction "5_5") (pintype "passive"))
      (node (ref "U2") (pin "8") (pinfunction "IO32_8") (pintype "bidirectional"))
    )
    (net (code "74") (name "TXD_LED") (class "Default")
      (node (ref "IC3") (pin "55") (pinfunction "BCBUS4_55") (pintype "bidirectional"))
      (node (ref "LED3") (pin "K") (pinfunction "C_K") (pintype "output"))
    )
    (net (code "75") (name "TXD_SPI_PROM_CLK") (class "Default")
      (node (ref "IC3") (pin "38") (pinfunction "BDBUS0_38") (pintype "bidirectional"))
      (node (ref "J1") (pin "10") (pinfunction "10_10") (pintype "passive"))
      (node (ref "J2") (pin "4") (pinfunction "4_4") (pintype "passive"))
      (node (ref "R14") (pin "2") (pinfunction "2_2") (pintype "passive"))
    )
    (net (code "76") (name "USB_DM") (class "Default")
      (node (ref "IC3") (pin "7") (pinfunction "DM_7") (pintype "bidirectional"))
      (node (ref "U$2") (pin "D-") (pinfunction "D-_D-") (pintype "bidirectional"))
    )
    (net (code "77") (name "USB_DP") (class "Default")
      (node (ref "IC3") (pin "8") (pinfunction "DP_8") (pintype "bidirectional"))
      (node (ref "U$2") (pin "D+") (pinfunction "D+_D+") (pintype "bidirectional"))
    )
    (net (code "78") (name "VBAT") (class "Default")
      (node (ref "C26") (pin "1") (pinfunction "1_1") (pintype "passive"))
      (node (ref "C27") (pin "1") (pinfunction "1_1") (pintype "passive"))
      (node (ref "C28") (pin "1") (pinfunction "1_1") (pintype "passive"))
      (node (ref "C29") (pin "1") (pinfunction "1_1") (pintype "passive"))
      (node (ref "C32") (pin "1") (pinfunction "1_1") (pintype "passive"))
      (node (ref "C33") (pin "1") (pinfunction "1_1") (pintype "passive"))
      (node (ref "C4") (pin "1") (pinfunction "1_1") (pintype "passive"))
      (node (ref "IC1") (pin "8") (pinfunction "VCC_8") (pintype "power_in"))
      (node (ref "IC2") (pin "4") (pinfunction "VIN_4") (pintype "bidirectional"))
      (node (ref "IC5") (pin "1") (pinfunction "VDD_1") (pintype "power_in"))
      (node (ref "IC6") (pin "1") (pinfunction "VDD_1") (pintype "power_in"))
      (node (ref "IC7") (pin "1") (pinfunction "VDD_1") (pintype "power_in"))
      (node (ref "IC8") (pin "1") (pinfunction "VDD_1") (pintype "power_in"))
      (node (ref "OFF/ON") (pin "3") (pinfunction "S_3") (pintype "passive"))
      (node (ref "R16") (pin "2") (pinfunction "2_2") (pintype "passive"))
      (node (ref "RESETTABLE_FUSE") (pin "2") (pinfunction "2_2") (pintype "passive"))
    )
    (net (code "79") (name "VCC") (class "Default")
      (node (ref "C1") (pin "1") (pinfunction "1_1") (pintype "passive"))
      (node (ref "C11") (pin "1") (pinfunction "1_1") (pintype "passive"))
      (node (ref "C14") (pin "1") (pinfunction "1_1") (pintype "passive"))
      (node (ref "C15") (pin "1") (pinfunction "1_1") (pintype "passive"))
      (node (ref "C16") (pin "1") (pinfunction "1_1") (pintype "passive"))
      (node (ref "C3") (pin "1") (pinfunction "1_1") (pintype "passive"))
      (node (ref "C35") (pin "1") (pinfunction "1_1") (pintype "passive"))
      (node (ref "C5") (pin "1") (pinfunction "1_1") (pintype "passive"))
      (node (ref "C8") (pin "1") (pinfunction "1_1") (pintype "passive"))
      (node (ref "D1") (pin "A") (pinfunction "A_A") (pintype "passive"))
      (node (ref "EMIFILTER1") (pin "1") (pinfunction "IN/OUT_1") (pintype "bidirectional"))
      (node (ref "EMIFILTER2") (pin "1") (pinfunction "IN/OUT_1") (pintype "bidirectional"))
      (node (ref "IC2") (pin "1") (pinfunction "VOUT_1") (pintype "bidirectional"))
      (node (ref "IC3") (pin "20") (pinfunction "VCCIO_1_20") (pintype "bidirectional"))
      (node (ref "IC3") (pin "31") (pinfunction "VCCIO_2_31") (pintype "bidirectional"))
      (node (ref "IC3") (pin "42") (pinfunction "VCCIO_3_42") (pintype "bidirectional"))
      (node (ref "IC3") (pin "50") (pinfunction "VREGIN_50") (pintype "bidirectional"))
      (node (ref "IC3") (pin "56") (pinfunction "VCCIO_4_56") (pintype "bidirectional"))
      (node (ref "IC4") (pin "6") (pinfunction "VCC_6") (pintype "power_in"))
      (node (ref "J1") (pin "1") (pinfunction "1_1") (pintype "passive"))
      (node (ref "J2") (pin "6") (pinfunction "6_6") (pintype "passive"))
      (node (ref "R1") (pin "2") (pinfunction "2_2") (pintype "passive"))
      (node (ref "R11") (pin "2") (pinfunction "2_2") (pintype "passive"))
      (node (ref "R12") (pin "2") (pinfunction "2_2") (pintype "passive"))
      (node (ref "R15") (pin "1") (pinfunction "1_1") (pintype "passive"))
      (node (ref "R18") (pin "1") (pinfunction "1_1") (pintype "passive"))
      (node (ref "R4") (pin "2") (pinfunction "2_2") (pintype "passive"))
      (node (ref "R5") (pin "1") (pinfunction "1_1") (pintype "passive"))
      (node (ref "R7") (pin "2") (pinfunction "2_2") (pintype "passive"))
      (node (ref "R8") (pin "1") (pinfunction "1_1") (pintype "passive"))
      (node (ref "R9") (pin "2") (pinfunction "2_2") (pintype "passive"))
      (node (ref "U$1") (pin "VCC") (pinfunction "VCC_VCC") (pintype "power_in"))
      (node (ref "U2") (pin "2") (pinfunction "3V3_2") (pintype "bidirectional"))
    )
    (net (code "80") (name "VCC1.8") (class "Default")
      (node (ref "C10") (pin "1") (pinfunction "1_1") (pintype "passive"))
      (node (ref "C12") (pin "1") (pinfunction "1_1") (pintype "passive"))
      (node (ref "C17") (pin "1") (pinfunction "1_1") (pintype "passive"))
      (node (ref "C9") (pin "1") (pinfunction "1_1") (pintype "passive"))
      (node (ref "IC3") (pin "12") (pinfunction "VCORE_1_12") (pintype "bidirectional"))
      (node (ref "IC3") (pin "37") (pinfunction "VCORE_2_37") (pintype "bidirectional"))
      (node (ref "IC3") (pin "49") (pinfunction "VREGOUT_49") (pintype "bidirectional"))
      (node (ref "IC3") (pin "64") (pinfunction "VCORE_3_64") (pintype "bidirectional"))
    )
    (net (code "81") (name "VCC5V") (class "Default")
      (node (ref "C13") (pin "2") (pinfunction "2_2") (pintype "passive"))
      (node (ref "IC-IP5305") (pin "VIN") (pinfunction "1_VIN") (pintype "power_in"))
      (node (ref "R2") (pin "1") (pinfunction "1_1") (pintype "passive"))
      (node (ref "U$2") (pin "+5V") (pinfunction "+5V_+5V") (pintype "bidirectional"))
    )
    (net (code "82") (name "unconnected-(IC2-ADJ-Pad8)") (class "Default")
      (node (ref "IC2") (pin "8") (pinfunction "ADJ_8") (pintype "bidirectional"))
    )
    (net (code "83") (name "unconnected-(IC3-ACBUS0-Pad26)") (class "Default")
      (node (ref "IC3") (pin "26") (pinfunction "ACBUS0_26") (pintype "bidirectional"))
    )
    (net (code "84") (name "unconnected-(IC3-ACBUS1-Pad27)") (class "Default")
      (node (ref "IC3") (pin "27") (pinfunction "ACBUS1_27") (pintype "bidirectional"))
    )
    (net (code "85") (name "unconnected-(IC3-ACBUS2-Pad28)") (class "Default")
      (node (ref "IC3") (pin "28") (pinfunction "ACBUS2_28") (pintype "bidirectional"))
    )
    (net (code "86") (name "unconnected-(IC3-ACBUS3-Pad29)") (class "Default")
      (node (ref "IC3") (pin "29") (pinfunction "ACBUS3_29") (pintype "bidirectional"))
    )
    (net (code "87") (name "unconnected-(IC3-ACBUS4-Pad30)") (class "Default")
      (node (ref "IC3") (pin "30") (pinfunction "ACBUS4_30") (pintype "bidirectional"))
    )
    (net (code "88") (name "unconnected-(IC3-ACBUS5-Pad32)") (class "Default")
      (node (ref "IC3") (pin "32") (pinfunction "ACBUS5_32") (pintype "bidirectional"))
    )
    (net (code "89") (name "unconnected-(IC3-ACBUS6-Pad33)") (class "Default")
      (node (ref "IC3") (pin "33") (pinfunction "ACBUS6_33") (pintype "bidirectional"))
    )
    (net (code "90") (name "unconnected-(IC3-ACBUS7-Pad34)") (class "Default")
      (node (ref "IC3") (pin "34") (pinfunction "ACBUS7_34") (pintype "bidirectional"))
    )
    (net (code "91") (name "unconnected-(IC3-ADBUS4-Pad21)") (class "Default")
      (node (ref "IC3") (pin "21") (pinfunction "ADBUS4_21") (pintype "bidirectional"))
    )
    (net (code "92") (name "unconnected-(IC3-ADBUS5-Pad22)") (class "Default")
      (node (ref "IC3") (pin "22") (pinfunction "ADBUS5_22") (pintype "bidirectional"))
    )
    (net (code "93") (name "unconnected-(IC3-ADBUS6-Pad23)") (class "Default")
      (node (ref "IC3") (pin "23") (pinfunction "ADBUS6_23") (pintype "bidirectional"))
    )
    (net (code "94") (name "unconnected-(IC3-ADBUS7-Pad24)") (class "Default")
      (node (ref "IC3") (pin "24") (pinfunction "ADBUS7_24") (pintype "bidirectional"))
    )
    (net (code "95") (name "unconnected-(IC3-BCBUS0-Pad48)") (class "Default")
      (node (ref "IC3") (pin "48") (pinfunction "BCBUS0_48") (pintype "bidirectional"))
    )
    (net (code "96") (name "unconnected-(IC3-BCBUS1-Pad52)") (class "Default")
      (node (ref "IC3") (pin "52") (pinfunction "BCBUS1_52") (pintype "bidirectional"))
    )
    (net (code "97") (name "unconnected-(IC3-BCBUS2-Pad53)") (class "Default")
      (node (ref "IC3") (pin "53") (pinfunction "BCBUS2_53") (pintype "bidirectional"))
    )
    (net (code "98") (name "unconnected-(IC3-BCBUS5-Pad57)") (class "Default")
      (node (ref "IC3") (pin "57") (pinfunction "BCBUS5_57") (pintype "bidirectional"))
    )
    (net (code "99") (name "unconnected-(IC3-BCBUS6-Pad58)") (class "Default")
      (node (ref "IC3") (pin "58") (pinfunction "BCBUS6_58") (pintype "bidirectional"))
    )
    (net (code "100") (name "unconnected-(IC3-BDBUS4-Pad43)") (class "Default")
      (node (ref "IC3") (pin "43") (pinfunction "BDBUS4_43") (pintype "bidirectional"))
    )
    (net (code "101") (name "unconnected-(IC3-BDBUS5-Pad44)") (class "Default")
      (node (ref "IC3") (pin "44") (pinfunction "BDBUS5_44") (pintype "bidirectional"))
    )
    (net (code "102") (name "unconnected-(IC3-BDBUS6-Pad45)") (class "Default")
      (node (ref "IC3") (pin "45") (pinfunction "BDBUS6_45") (pintype "bidirectional"))
    )
    (net (code "103") (name "unconnected-(IC3-BDBUS7-Pad46)") (class "Default")
      (node (ref "IC3") (pin "46") (pinfunction "BDBUS7_46") (pintype "bidirectional"))
    )
    (net (code "104") (name "unconnected-(IC8-DOUT-Pad2)") (class "Default")
      (node (ref "IC8") (pin "2") (pinfunction "DOUT_2") (pintype "output"))
    )
    (net (code "105") (name "unconnected-(U$1-NC_1-PadNC1)") (class "Default")
      (node (ref "U$1") (pin "NC1") (pinfunction "NC_1_NC1") (pintype "no_connect"))
    )
    (net (code "106") (name "unconnected-(U$1-NC_2-PadNC2)") (class "Default")
      (node (ref "U$1") (pin "NC2") (pinfunction "NC_2_NC2") (pintype "no_connect"))
    )
    (net (code "107") (name "unconnected-(U$1-NC_3-PadNC3)") (class "Default")
      (node (ref "U$1") (pin "NC3") (pinfunction "NC_3_NC3") (pintype "no_connect"))
    )
    (net (code "108") (name "unconnected-(U$1-NC_4-PadNC4)") (class "Default")
      (node (ref "U$1") (pin "NC4") (pinfunction "NC_4_NC4") (pintype "no_connect"))
    )
    (net (code "109") (name "unconnected-(U$2-PadID)") (class "Default")
      (node (ref "U$2") (pin "ID") (pinfunction "ID_ID") (pintype "bidirectional"))
    )
    (net (code "110") (name "unconnected-(U2-CLK-Pad20)") (class "Default")
      (node (ref "U2") (pin "20") (pinfunction "CLK_20") (pintype "bidirectional"))
    )
    (net (code "111") (name "unconnected-(U2-CMD-Pad19)") (class "Default")
      (node (ref "U2") (pin "19") (pinfunction "CMD_19") (pintype "bidirectional"))
    )
    (net (code "112") (name "unconnected-(U2-NC-Pad32)") (class "Default")
      (node (ref "U2") (pin "32") (pinfunction "NC_32") (pintype "bidirectional"))
    )
    (net (code "113") (name "unconnected-(U2-SD1-Pad22)") (class "Default")
      (node (ref "U2") (pin "22") (pinfunction "SD1_22") (pintype "bidirectional"))
    )
    (net (code "114") (name "unconnected-(U2-SD2-Pad17)") (class "Default")
      (node (ref "U2") (pin "17") (pinfunction "SD2_17") (pintype "bidirectional"))
    )
    (net (code "115") (name "unconnected-(U2-SD3-Pad18)") (class "Default")
      (node (ref "U2") (pin "18") (pinfunction "SD3_18") (pintype "bidirectional"))
    )
    (net (code "116") (name "unconnected-(U2-SDO-Pad21)") (class "Default")
      (node (ref "U2") (pin "21") (pinfunction "SDO_21") (pintype "bidirectional"))
    )
  )
)
